# FET_driver.net
KiCad netlist of a schematic drawn in EAGLE
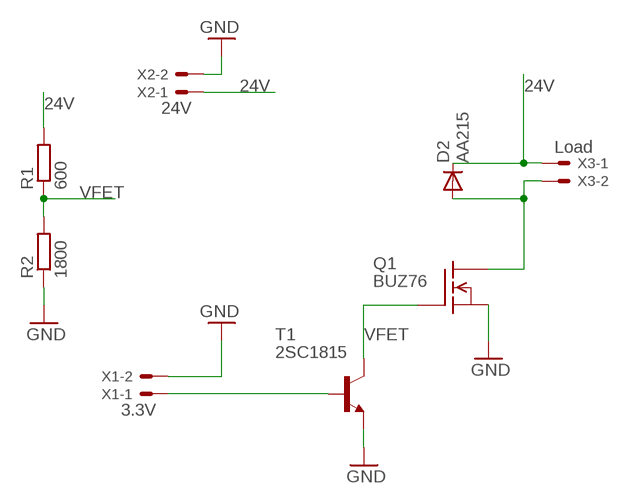
[diagram p0: schematic, sheet 1]

(export (version "E")
  (design (tool "Eeschema 10.0.6"))
  (components
    (comp (ref "D2")
      (value "AA215")
      (footprint "eagle-import:DO07")
      (libsource (lib "eagle-import") (part "AA215"))
    )
    (comp (ref "Q1")
      (value "BUZ76")
      (footprint "eagle-import:TO220")
      (libsource (lib "eagle-import") (part "BUZ72"))
    )
    (comp (ref "R1")
      (value "600")
      (footprint "eagle-import:0207_10")
      (libsource (lib "eagle-import") (part "R-EU_0207/10"))
    )
    (comp (ref "R2")
      (value "1800")
      (footprint "eagle-import:0207_10")
      (libsource (lib "eagle-import") (part "R-EU_0207/10"))
    )
    (comp (ref "T1")
      (value "2SC1815")
      (footprint "eagle-import:TO92-ECB")
      (libsource (lib "eagle-import") (part "2SC1815"))
    )
    (comp (ref "X1")
      (value "3.3V")
      (footprint "eagle-import:22-23-2021")
      (fields (field (name "MF") "MOLEX") (field (name "MPN") "22-23-2021"))
      (libsource (lib "eagle-import") (part "22-23-2021"))
    )
    (comp (ref "X2")
      (value "24V")
      (footprint "eagle-import:22-23-2021")
      (fields (field (name "MF") "MOLEX") (field (name "MPN") "22-23-2021"))
      (libsource (lib "eagle-import") (part "22-23-2021"))
    )
    (comp (ref "X3")
      (value "Load")
      (footprint "eagle-import:22-23-2021")
      (fields (field (name "MF") "MOLEX") (field (name "MPN") "22-23-2021"))
      (libsource (lib "eagle-import") (part "22-23-2021"))
    )
  )
  (nets
    (net (code "1") (name "/24V") (class "Default")
      (node (ref "D2") (pin "C") (pinfunction "C_C") (pintype "passive"))
      (node (ref "R1") (pin "2") (pinfunction "2_2") (pintype "passive"))
      (node (ref "X2") (pin "1") (pinfunction "S_1") (pintype "passive"))
      (node (ref "X3") (pin "1") (pinfunction "S_1") (pintype "passive"))
    )
    (net (code "2") (name "/VFET") (class "Default")
      (node (ref "Q1") (pin "1") (pinfunction "G_1") (pintype "passive"))
      (node (ref "R1") (pin "1") (pinfunction "1_1") (pintype "passive"))
      (node (ref "R2") (pin "2") (pinfunction "2_2") (pintype "passive"))
      (node (ref "T1") (pin "C") (pinfunction "C_C") (pintype "passive"))
    )
    (net (code "3") (name "GND") (class "Default")
      (node (ref "Q1") (pin "3") (pinfunction "S_3") (pintype "passive"))
      (node (ref "R2") (pin "1") (pinfunction "1_1") (pintype "passive"))
      (node (ref "T1") (pin "E") (pinfunction "E_E") (pintype "passive"))
      (node (ref "X1") (pin "2") (pinfunction "S_2") (pintype "passive"))
      (node (ref "X2") (pin "2") (pinfunction "S_2") (pintype "passive"))
    )
    (net (code "4") (name "Net-(Q1-D)") (class "Default")
      (node (ref "D2") (pin "A") (pinfunction "A_A") (pintype "passive"))
      (node (ref "Q1") (pin "2") (pinfunction "D_2") (pintype "passive"))
      (node (ref "X3") (pin "2") (pinfunction "S_2") (pintype "passive"))
    )
    (net (code "5") (name "Net-(X1A-S)") (class "Default")
      (node (ref "T1") (pin "B") (pinfunction "B_B") (pintype "passive"))
      (node (ref "X1") (pin "1") (pinfunction "S_1") (pintype "passive"))
    )
  )
)
